# GEN.net
KiCad netlist of a schematic drawn in Altium Designer
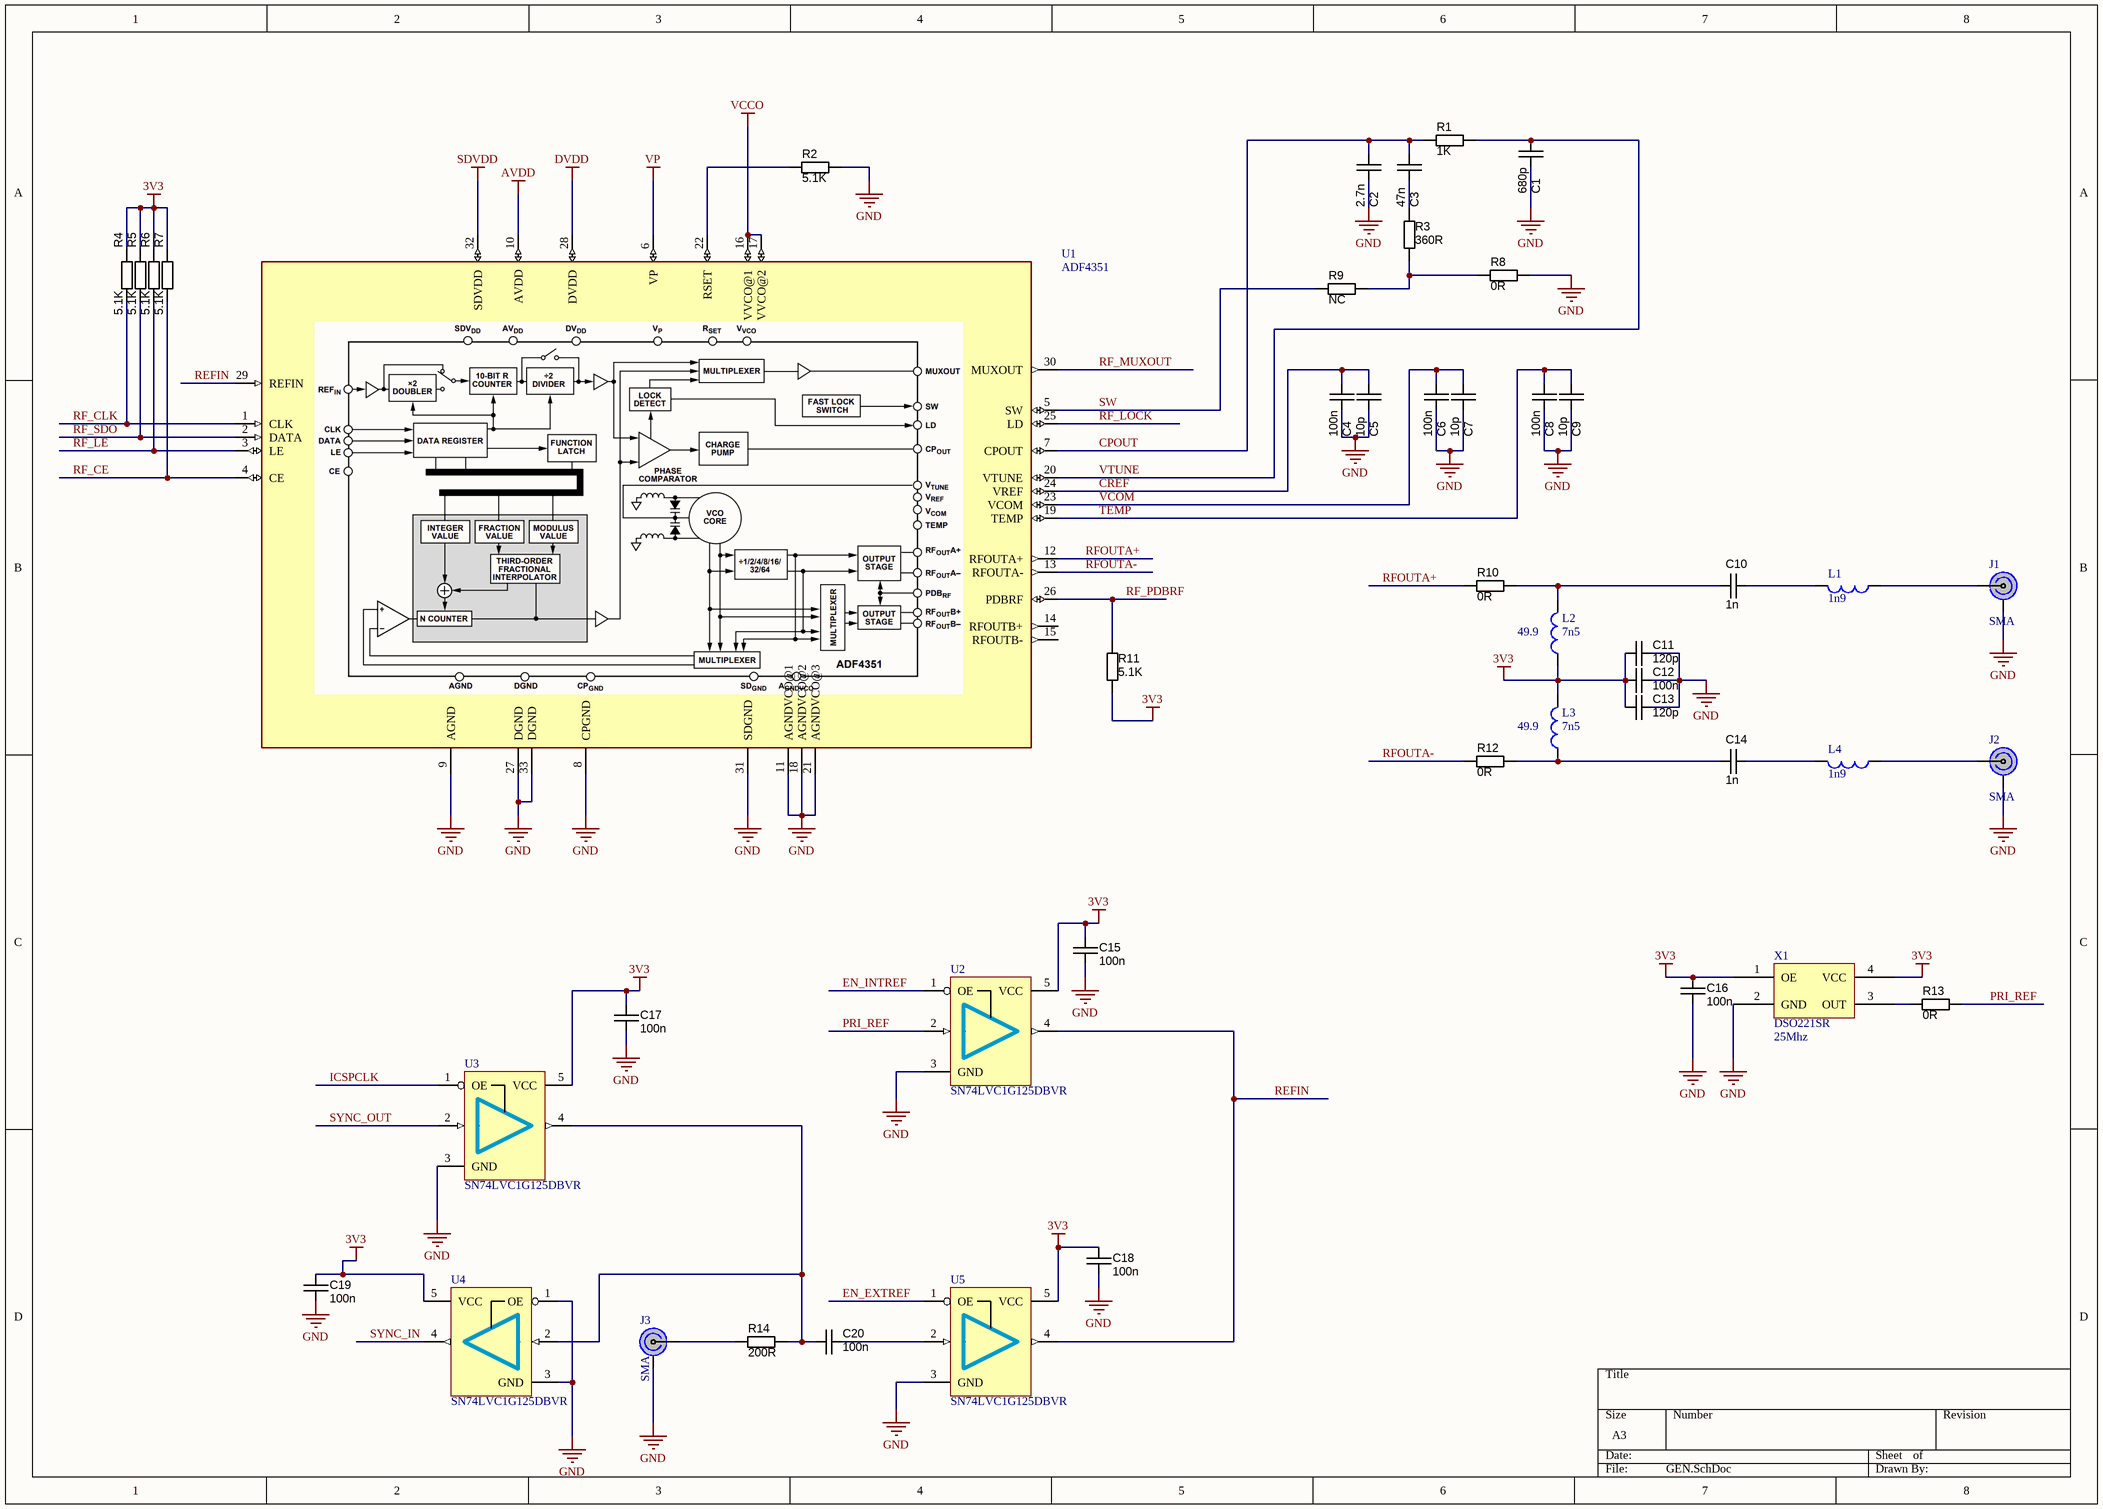
[diagram p0: GEN.SchDoc]

(export (version "E")
  (design (tool "Eeschema 10.0.6"))
  (components
    (comp (ref "C1")
      (value "680p")
      (footprint "CAPC1005N")
      (description "Capacitor SMD Cer 10nF 10% 16V X7R 0402")
      (fields (field (name "TOLERANCE") "±10%"))
      (libsource (lib "PBL - Capacitors") (part "CAPC_10n_0402_16V_10%"))
    )
    (comp (ref "C2")
      (value "2.7n")
      (footprint "CAPC1005N")
      (description "Capacitor SMD Cer 10nF 10% 16V X7R 0402")
      (fields (field (name "TOLERANCE") "±10%"))
      (libsource (lib "PBL - Capacitors") (part "CAPC_10n_0402_16V_10%"))
    )
    (comp (ref "C3")
      (value "47n")
      (footprint "CAPC1005N")
      (description "Capacitor SMD Cer 10nF 10% 16V X7R 0402")
      (fields (field (name "TOLERANCE") "±10%"))
      (libsource (lib "PBL - Capacitors") (part "CAPC_10n_0402_16V_10%"))
    )
    (comp (ref "C4")
      (value "100n")
      (footprint "CAPC1005N")
      (description "Capacitor SMD Cer 10nF 10% 16V X7R 0402")
      (fields (field (name "TOLERANCE") "±10%"))
      (libsource (lib "PBL - Capacitors") (part "CAPC_10n_0402_16V_10%"))
    )
    (comp (ref "C5")
      (value "10p")
      (footprint "CAPC1005N")
      (description "Capacitor SMD Cer 10nF 10% 16V X7R 0402")
      (fields (field (name "TOLERANCE") "±10%"))
      (libsource (lib "PBL - Capacitors") (part "CAPC_10n_0402_16V_10%"))
    )
    (comp (ref "C6")
      (value "100n")
      (footprint "CAPC1005N")
      (description "Capacitor SMD Cer 10nF 10% 16V X7R 0402")
      (fields (field (name "TOLERANCE") "±10%"))
      (libsource (lib "PBL - Capacitors") (part "CAPC_10n_0402_16V_10%"))
    )
    (comp (ref "C7")
      (value "10p")
      (footprint "CAPC1005N")
      (description "Capacitor SMD Cer 10nF 10% 16V X7R 0402")
      (fields (field (name "TOLERANCE") "±10%"))
      (libsource (lib "PBL - Capacitors") (part "CAPC_10n_0402_16V_10%"))
    )
    (comp (ref "C8")
      (value "100n")
      (footprint "CAPC1005N")
      (description "Capacitor SMD Cer 10nF 10% 16V X7R 0402")
      (fields (field (name "TOLERANCE") "±10%"))
      (libsource (lib "PBL - Capacitors") (part "CAPC_10n_0402_16V_10%"))
    )
    (comp (ref "C9")
      (value "10p")
      (footprint "CAPC1005N")
      (description "Capacitor SMD Cer 10nF 10% 16V X7R 0402")
      (fields (field (name "TOLERANCE") "±10%"))
      (libsource (lib "PBL - Capacitors") (part "CAPC_10n_0402_16V_10%"))
    )
    (comp (ref "C10")
      (value "1n")
      (footprint "CAPC1005N")
      (description "Capacitor SMD Cer 10nF 10% 16V X7R 0402")
      (fields (field (name "TOLERANCE") "±10%"))
      (libsource (lib "PBL - Capacitors") (part "CAPC_10n_0402_16V_10%"))
    )
    (comp (ref "C11")
      (value "120p")
      (footprint "CAPC1005N")
      (description "Capacitor SMD Cer 10nF 10% 16V X7R 0402")
      (fields (field (name "TOLERANCE") "±10%"))
      (libsource (lib "PBL - Capacitors") (part "CAPC_10n_0402_16V_10%"))
    )
    (comp (ref "C12")
      (value "100n")
      (footprint "CAPC1005N")
      (description "Capacitor SMD Cer 10nF 10% 16V X7R 0402")
      (fields (field (name "TOLERANCE") "±10%"))
      (libsource (lib "PBL - Capacitors") (part "CAPC_10n_0402_16V_10%"))
    )
    (comp (ref "C13")
      (value "120p")
      (footprint "CAPC1005N")
      (description "Capacitor SMD Cer 10nF 10% 16V X7R 0402")
      (fields (field (name "TOLERANCE") "±10%"))
      (libsource (lib "PBL - Capacitors") (part "CAPC_10n_0402_16V_10%"))
    )
    (comp (ref "C14")
      (value "1n")
      (footprint "CAPC1005N")
      (description "Capacitor SMD Cer 10nF 10% 16V X7R 0402")
      (fields (field (name "TOLERANCE") "±10%"))
      (libsource (lib "PBL - Capacitors") (part "CAPC_10n_0402_16V_10%"))
    )
    (comp (ref "C15")
      (value "100n")
      (footprint "CAPC1005N")
      (description "Capacitor SMD Cer 10nF 10% 16V X7R 0402")
      (fields (field (name "TOLERANCE") "±10%"))
      (libsource (lib "PBL - Capacitors") (part "CAPC_10n_0402_16V_10%"))
    )
    (comp (ref "C16")
      (value "100n")
      (footprint "CAPC1005N")
      (description "Capacitor SMD Cer 10nF 10% 16V X7R 0402")
      (fields (field (name "TOLERANCE") "±10%"))
      (libsource (lib "PBL - Capacitors") (part "CAPC_10n_0402_16V_10%"))
    )
    (comp (ref "C17")
      (value "100n")
      (footprint "CAPC1005N")
      (description "Capacitor SMD Cer 10nF 10% 16V X7R 0402")
      (fields (field (name "TOLERANCE") "±10%"))
      (libsource (lib "PBL - Capacitors") (part "CAPC_10n_0402_16V_10%"))
    )
    (comp (ref "C18")
      (value "100n")
      (footprint "CAPC1005N")
      (description "Capacitor SMD Cer 10nF 10% 16V X7R 0402")
      (fields (field (name "TOLERANCE") "±10%"))
      (libsource (lib "PBL - Capacitors") (part "CAPC_10n_0402_16V_10%"))
    )
    (comp (ref "C19")
      (value "100n")
      (footprint "CAPC1005N")
      (description "Capacitor SMD Cer 10nF 10% 16V X7R 0402")
      (fields (field (name "TOLERANCE") "±10%"))
      (libsource (lib "PBL - Capacitors") (part "CAPC_10n_0402_16V_10%"))
    )
    (comp (ref "C20")
      (value "100n")
      (footprint "CAPC1005N")
      (description "Capacitor SMD Cer 10nF 10% 16V X7R 0402")
      (fields (field (name "TOLERANCE") "±10%"))
      (libsource (lib "PBL - Capacitors") (part "CAPC_10n_0402_16V_10%"))
    )
    (comp (ref "J1") (value "SMA") (footprint "BWSMA-KWE-Z001") (libsource (lib "") (part "SMA Connector_1")))
    (comp (ref "J2") (value "SMA") (footprint "BWSMA-KWE-Z001") (libsource (lib "") (part "SMA Connector_1")))
    (comp (ref "J3")
      (value "SMA")
      (footprint "BWSMA-KWE-Z001")
      (libsource (lib "cvlib") (part "SMA Connector"))
    )
    (comp (ref "L1")
      (value "1n9")
      (footprint "0402_Inductor")
      (libsource (lib "cvlib") (part "inductor_smd"))
    )
    (comp (ref "L2")
      (value "7n5")
      (footprint "0402_Inductor")
      (libsource (lib "cvlib") (part "inductor_smd"))
    )
    (comp (ref "L3")
      (value "7n5")
      (footprint "0402_Inductor")
      (libsource (lib "cvlib") (part "inductor_smd"))
    )
    (comp (ref "L4")
      (value "1n9")
      (footprint "0402_Inductor")
      (libsource (lib "cvlib") (part "inductor_smd"))
    )
    (comp (ref "R1")
      (value "1K")
      (footprint "RESC1005N")
      (description "Resistor SMD chip 3.3k Ohm 0.063W 5% 0402")
      (fields (field (name "TOLERANCE") "±5%") (field (name "Comment") "Thick Film"))
      (libsource (lib "") (part "RES_3K3_0402_5%_1"))
    )
    (comp (ref "R2")
      (value "5.1K")
      (footprint "RESC1005N")
      (description "Resistor SMD chip 3.3k Ohm 0.063W 5% 0402")
      (fields (field (name "TOLERANCE") "±5%") (field (name "Comment") "Thick Film"))
      (libsource (lib "") (part "RES_3K3_0402_5%_1"))
    )
    (comp (ref "R3")
      (value "360R")
      (footprint "RESC1005N")
      (description "Resistor SMD chip 3.3k Ohm 0.063W 5% 0402")
      (fields (field (name "TOLERANCE") "±5%") (field (name "Comment") "Thick Film"))
      (libsource (lib "PBL - Resistors") (part "RES_3K3_0402_5%"))
    )
    (comp (ref "R4")
      (value "5.1K")
      (footprint "RESC1005N")
      (description "Resistor SMD chip 3.3k Ohm 0.063W 5% 0402")
      (fields (field (name "TOLERANCE") "±5%") (field (name "Comment") "Thick Film"))
      (libsource (lib "PBL - Resistors") (part "RES_3K3_0402_5%"))
    )
    (comp (ref "R5")
      (value "5.1K")
      (footprint "RESC1005N")
      (description "Resistor SMD chip 3.3k Ohm 0.063W 5% 0402")
      (fields (field (name "TOLERANCE") "±5%") (field (name "Comment") "Thick Film"))
      (libsource (lib "PBL - Resistors") (part "RES_3K3_0402_5%"))
    )
    (comp (ref "R6")
      (value "5.1K")
      (footprint "RESC1005N")
      (description "Resistor SMD chip 3.3k Ohm 0.063W 5% 0402")
      (fields (field (name "TOLERANCE") "±5%") (field (name "Comment") "Thick Film"))
      (libsource (lib "PBL - Resistors") (part "RES_3K3_0402_5%"))
    )
    (comp (ref "R7")
      (value "5.1K")
      (footprint "RESC1005N")
      (description "Resistor SMD chip 3.3k Ohm 0.063W 5% 0402")
      (fields (field (name "TOLERANCE") "±5%") (field (name "Comment") "Thick Film"))
      (libsource (lib "PBL - Resistors") (part "RES_3K3_0402_5%"))
    )
    (comp (ref "R8")
      (value "0R")
      (footprint "RESC1005N")
      (description "Resistor SMD chip 3.3k Ohm 0.063W 5% 0402")
      (fields (field (name "TOLERANCE") "±5%") (field (name "Comment") "Thick Film"))
      (libsource (lib "") (part "RES_3K3_0402_5%_2"))
    )
    (comp (ref "R9")
      (value "NC")
      (footprint "RESC1005N")
      (description "Resistor SMD chip 3.3k Ohm 0.063W 5% 0402")
      (fields (field (name "TOLERANCE") "±5%") (field (name "Comment") "Thick Film"))
      (libsource (lib "") (part "RES_3K3_0402_5%_2"))
    )
    (comp (ref "R10")
      (value "0R")
      (footprint "RESC1005N")
      (description "Resistor SMD chip 3.3k Ohm 0.063W 5% 0402")
      (fields (field (name "TOLERANCE") "±5%") (field (name "Comment") "Thick Film"))
      (libsource (lib "") (part "RES_3K3_0402_5%_1"))
    )
    (comp (ref "R11")
      (value "5.1K")
      (footprint "RESC1005N")
      (description "Resistor SMD chip 3.3k Ohm 0.063W 5% 0402")
      (fields (field (name "TOLERANCE") "±5%") (field (name "Comment") "Thick Film"))
      (libsource (lib "PBL - Resistors") (part "RES_3K3_0402_5%"))
    )
    (comp (ref "R12")
      (value "0R")
      (footprint "RESC1005N")
      (description "Resistor SMD chip 3.3k Ohm 0.063W 5% 0402")
      (fields (field (name "TOLERANCE") "±5%") (field (name "Comment") "Thick Film"))
      (libsource (lib "") (part "RES_3K3_0402_5%_1"))
    )
    (comp (ref "R13")
      (value "0R")
      (footprint "RESC1005N")
      (description "Resistor SMD chip 3.3k Ohm 0.063W 5% 0402")
      (fields (field (name "TOLERANCE") "±5%") (field (name "Comment") "Thick Film"))
      (libsource (lib "") (part "RES_3K3_0402_5%_1"))
    )
    (comp (ref "R14")
      (value "200R")
      (footprint "RESC1005N")
      (description "Resistor SMD chip 3.3k Ohm 0.063W 5% 0402")
      (fields (field (name "TOLERANCE") "±5%") (field (name "Comment") "Thick Film"))
      (libsource (lib "") (part "RES_3K3_0402_5%_1"))
    )
    (comp (ref "U1")
      (value "ADF4351")
      (footprint "VQFN32")
      (fields (field (name "MF") "Analog Devices, Inc."))
      (libsource (lib "cvlib") (part "ADF4351"))
    )
    (comp (ref "U2")
      (value "SN74LVC1G125DBVR")
      (footprint "SOT23-5")
      (description "LVC Tristate buffer")
      (libsource (lib "cvlib") (part "SN74LVC1G125DBVR"))
    )
    (comp (ref "U3")
      (value "SN74LVC1G125DBVR")
      (footprint "SOT23-5")
      (description "LVC Tristate buffer")
      (libsource (lib "cvlib") (part "SN74LVC1G125DBVR"))
    )
    (comp (ref "U4")
      (value "SN74LVC1G125DBVR")
      (footprint "SOT23-5")
      (description "LVC Tristate buffer")
      (libsource (lib "") (part "SN74LVC1G125DBVR_1"))
    )
    (comp (ref "U5")
      (value "SN74LVC1G125DBVR")
      (footprint "SOT23-5")
      (description "LVC Tristate buffer")
      (libsource (lib "cvlib") (part "SN74LVC1G125DBVR"))
    )
    (comp (ref "X1")
      (value "DSO221SR")
      (footprint "Active Oscillator 2520")
      (description "Active Oscillator_2520")
      (fields (field (name "ALTIUM_VALUE") "25Mhz"))
      (libsource (lib "Crystal_and_oscillator") (part "Oscillator_2520"))
    )
  )
  (nets
    (net (code "1") (name "/CPOUT") (class "Default")
      (node (ref "C2") (pin "1") (pintype "passive"))
      (node (ref "C3") (pin "1") (pintype "passive"))
      (node (ref "R1") (pin "1") (pinfunction "1_1") (pintype "passive"))
      (node (ref "U1") (pin "7") (pinfunction "CPOUT_7") (pintype "bidirectional"))
    )
    (net (code "2") (name "/CREF") (class "Default")
      (node (ref "C4") (pin "1") (pintype "passive"))
      (node (ref "C5") (pin "1") (pintype "passive"))
      (node (ref "U1") (pin "24") (pinfunction "VREF_24") (pintype "bidirectional"))
    )
    (net (code "3") (name "/EN_EXTREF") (class "Default")
      (node (ref "U5") (pin "1") (pinfunction "OE_1") (pintype "power_in"))
    )
    (net (code "4") (name "/EN_INTREF") (class "Default")
      (node (ref "U2") (pin "1") (pinfunction "OE_1") (pintype "power_in"))
    )
    (net (code "5") (name "/ICSPCLK") (class "Default")
      (node (ref "U3") (pin "1") (pinfunction "OE_1") (pintype "power_in"))
    )
    (net (code "6") (name "/PRI_REF") (class "Default")
      (node (ref "R13") (pin "2") (pinfunction "2_2") (pintype "passive"))
      (node (ref "U2") (pin "2") (pinfunction "2_2") (pintype "input"))
    )
    (net (code "7") (name "/REFIN") (class "Default")
      (node (ref "U1") (pin "29") (pinfunction "REFIN_29") (pintype "input"))
      (node (ref "U2") (pin "4") (pinfunction "4_4") (pintype "output"))
      (node (ref "U5") (pin "4") (pinfunction "4_4") (pintype "output"))
    )
    (net (code "8") (name "/RFOUTA+") (class "Default")
      (node (ref "R10") (pin "1") (pinfunction "1_1") (pintype "passive"))
      (node (ref "U1") (pin "12") (pinfunction "RFOUTA+_12") (pintype "output"))
    )
    (net (code "9") (name "/RFOUTA-") (class "Default")
      (node (ref "R12") (pin "1") (pinfunction "1_1") (pintype "passive"))
      (node (ref "U1") (pin "13") (pinfunction "RFOUTA-_13") (pintype "output"))
    )
    (net (code "10") (name "/RF_CE") (class "Default")
      (node (ref "R7") (pin "1") (pinfunction "1_1") (pintype "passive"))
      (node (ref "U1") (pin "4") (pinfunction "CE_4") (pintype "bidirectional"))
    )
    (net (code "11") (name "/RF_CLK") (class "Default")
      (node (ref "R4") (pin "1") (pinfunction "1_1") (pintype "passive"))
      (node (ref "U1") (pin "1") (pinfunction "CLK_1") (pintype "input"))
    )
    (net (code "12") (name "/RF_LE") (class "Default")
      (node (ref "R6") (pin "1") (pinfunction "1_1") (pintype "passive"))
      (node (ref "U1") (pin "3") (pinfunction "LE_3") (pintype "bidirectional"))
    )
    (net (code "13") (name "/RF_LOCK") (class "Default")
      (node (ref "U1") (pin "25") (pinfunction "LD_25") (pintype "bidirectional"))
    )
    (net (code "14") (name "/RF_MUXOUT") (class "Default")
      (node (ref "U1") (pin "30") (pinfunction "MUXOUT_30") (pintype "output"))
    )
    (net (code "15") (name "/RF_PDBRF") (class "Default")
      (node (ref "R11") (pin "2") (pinfunction "2_2") (pintype "passive"))
      (node (ref "U1") (pin "26") (pinfunction "PDBRF_26") (pintype "bidirectional"))
    )
    (net (code "16") (name "/RF_SDO") (class "Default")
      (node (ref "R5") (pin "1") (pinfunction "1_1") (pintype "passive"))
      (node (ref "U1") (pin "2") (pinfunction "DATA_2") (pintype "input"))
    )
    (net (code "17") (name "/SW") (class "Default")
      (node (ref "R9") (pin "2") (pinfunction "2_2") (pintype "passive"))
      (node (ref "U1") (pin "5") (pinfunction "SW_5") (pintype "bidirectional"))
    )
    (net (code "18") (name "/SYNC_IN") (class "Default")
      (node (ref "U4") (pin "4") (pinfunction "4_4") (pintype "output"))
    )
    (net (code "19") (name "/SYNC_OUT") (class "Default")
      (node (ref "U3") (pin "2") (pinfunction "2_2") (pintype "input"))
    )
    (net (code "20") (name "/TEMP") (class "Default")
      (node (ref "C8") (pin "1") (pintype "passive"))
      (node (ref "C9") (pin "1") (pintype "passive"))
      (node (ref "U1") (pin "19") (pinfunction "TEMP_19") (pintype "bidirectional"))
    )
    (net (code "21") (name "/VCOM") (class "Default")
      (node (ref "C6") (pin "1") (pintype "passive"))
      (node (ref "C7") (pin "1") (pintype "passive"))
      (node (ref "U1") (pin "23") (pinfunction "VCOM_23") (pintype "bidirectional"))
    )
    (net (code "22") (name "/VTUNE") (class "Default")
      (node (ref "C1") (pin "1") (pintype "passive"))
      (node (ref "R1") (pin "2") (pinfunction "2_2") (pintype "passive"))
      (node (ref "U1") (pin "20") (pinfunction "VTUNE_20") (pintype "bidirectional"))
    )
    (net (code "23") (name "3V3") (class "Default")
      (node (ref "C11") (pin "2") (pintype "passive"))
      (node (ref "C12") (pin "2") (pintype "passive"))
      (node (ref "C13") (pin "2") (pintype "passive"))
      (node (ref "C15") (pin "2") (pintype "passive"))
      (node (ref "C16") (pin "2") (pintype "passive"))
      (node (ref "C17") (pin "2") (pintype "passive"))
      (node (ref "C18") (pin "2") (pintype "passive"))
      (node (ref "C19") (pin "2") (pintype "passive"))
      (node (ref "L2") (pin "1") (pinfunction "1_1") (pintype "passive"))
      (node (ref "L3") (pin "2") (pinfunction "2_2") (pintype "passive"))
      (node (ref "R11") (pin "1") (pinfunction "1_1") (pintype "passive"))
      (node (ref "R4") (pin "2") (pinfunction "2_2") (pintype "passive"))
      (node (ref "R5") (pin "2") (pinfunction "2_2") (pintype "passive"))
      (node (ref "R6") (pin "2") (pinfunction "2_2") (pintype "passive"))
      (node (ref "R7") (pin "2") (pinfunction "2_2") (pintype "passive"))
      (node (ref "U2") (pin "5") (pinfunction "VCC_5") (pintype "power_in"))
      (node (ref "U3") (pin "5") (pinfunction "VCC_5") (pintype "power_in"))
      (node (ref "U4") (pin "5") (pinfunction "VCC_5") (pintype "power_in"))
      (node (ref "U5") (pin "5") (pinfunction "VCC_5") (pintype "power_in"))
      (node (ref "X1") (pin "1") (pinfunction "OE_1") (pintype "passive"))
      (node (ref "X1") (pin "4") (pinfunction "VCC_4") (pintype "passive"))
    )
    (net (code "24") (name "AVDD") (class "Default")
      (node (ref "U1") (pin "10") (pinfunction "AVDD_10") (pintype "bidirectional"))
    )
    (net (code "25") (name "DVDD") (class "Default")
      (node (ref "U1") (pin "28") (pinfunction "DVDD_28") (pintype "bidirectional"))
    )
    (net (code "26") (name "GND") (class "Default")
      (node (ref "C1") (pin "2") (pintype "passive"))
      (node (ref "C11") (pin "1") (pintype "passive"))
      (node (ref "C12") (pin "1") (pintype "passive"))
      (node (ref "C13") (pin "1") (pintype "passive"))
      (node (ref "C15") (pin "1") (pintype "passive"))
      (node (ref "C16") (pin "1") (pintype "passive"))
      (node (ref "C17") (pin "1") (pintype "passive"))
      (node (ref "C18") (pin "1") (pintype "passive"))
      (node (ref "C19") (pin "1") (pintype "passive"))
      (node (ref "C2") (pin "2") (pintype "passive"))
      (node (ref "C4") (pin "2") (pintype "passive"))
      (node (ref "C5") (pin "2") (pintype "passive"))
      (node (ref "C6") (pin "2") (pintype "passive"))
      (node (ref "C7") (pin "2") (pintype "passive"))
      (node (ref "C8") (pin "2") (pintype "passive"))
      (node (ref "C9") (pin "2") (pintype "passive"))
      (node (ref "J1") (pin "2") (pinfunction "2_2") (pintype "passive"))
      (node (ref "J2") (pin "2") (pinfunction "2_2") (pintype "passive"))
      (node (ref "J3") (pin "2") (pinfunction "2_2") (pintype "passive"))
      (node (ref "R2") (pin "2") (pinfunction "2_2") (pintype "passive"))
      (node (ref "R8") (pin "1") (pinfunction "1_1") (pintype "passive"))
      (node (ref "U1") (pin "11") (pinfunction "AGNDVCO@1_11") (pintype "passive"))
      (node (ref "U1") (pin "18") (pinfunction "AGNDVCO@2_18") (pintype "passive"))
      (node (ref "U1") (pin "21") (pinfunction "AGNDVCO@3_21") (pintype "passive"))
      (node (ref "U1") (pin "27") (pinfunction "DGND_27") (pintype "passive"))
      (node (ref "U1") (pin "31") (pinfunction "SDGND_31") (pintype "passive"))
      (node (ref "U1") (pin "33") (pinfunction "DGND_33") (pintype "passive"))
      (node (ref "U1") (pin "8") (pinfunction "CPGND_8") (pintype "passive"))
      (node (ref "U1") (pin "9") (pinfunction "AGND_9") (pintype "passive"))
      (node (ref "U2") (pin "3") (pinfunction "GND_3") (pintype "power_in"))
      (node (ref "U3") (pin "3") (pinfunction "GND_3") (pintype "power_in"))
      (node (ref "U4") (pin "1") (pinfunction "OE_1") (pintype "power_in"))
      (node (ref "U4") (pin "3") (pinfunction "GND_3") (pintype "power_in"))
      (node (ref "U5") (pin "3") (pinfunction "GND_3") (pintype "power_in"))
      (node (ref "X1") (pin "2") (pinfunction "GND_2") (pintype "passive"))
    )
    (net (code "27") (name "Net-(C3-Pad2)") (class "Default")
      (node (ref "C3") (pin "2") (pintype "passive"))
      (node (ref "R3") (pin "2") (pinfunction "2_2") (pintype "passive"))
    )
    (net (code "28") (name "Net-(C10-Pad1)") (class "Default")
      (node (ref "C10") (pin "1") (pintype "passive"))
      (node (ref "L1") (pin "2") (pinfunction "2_2") (pintype "passive"))
    )
    (net (code "29") (name "Net-(C10-Pad2)") (class "Default")
      (node (ref "C10") (pin "2") (pintype "passive"))
      (node (ref "L2") (pin "2") (pinfunction "2_2") (pintype "passive"))
      (node (ref "R10") (pin "2") (pinfunction "2_2") (pintype "passive"))
    )
    (net (code "30") (name "Net-(C14-Pad1)") (class "Default")
      (node (ref "C14") (pin "1") (pintype "passive"))
      (node (ref "L4") (pin "2") (pinfunction "2_2") (pintype "passive"))
    )
    (net (code "31") (name "Net-(C14-Pad2)") (class "Default")
      (node (ref "C14") (pin "2") (pintype "passive"))
      (node (ref "L3") (pin "1") (pinfunction "1_1") (pintype "passive"))
      (node (ref "R12") (pin "2") (pinfunction "2_2") (pintype "passive"))
    )
    (net (code "32") (name "Net-(C20-Pad1)") (class "Default")
      (node (ref "C20") (pin "1") (pintype "passive"))
      (node (ref "U5") (pin "2") (pinfunction "2_2") (pintype "input"))
    )
    (net (code "33") (name "Net-(C20-Pad2)") (class "Default")
      (node (ref "C20") (pin "2") (pintype "passive"))
      (node (ref "R14") (pin "2") (pinfunction "2_2") (pintype "passive"))
      (node (ref "U3") (pin "4") (pinfunction "4_4") (pintype "output"))
      (node (ref "U4") (pin "2") (pinfunction "2_2") (pintype "input"))
    )
    (net (code "34") (name "Net-(J1-Pad1)") (class "Default")
      (node (ref "J1") (pin "1") (pinfunction "1_1") (pintype "passive"))
      (node (ref "L1") (pin "1") (pinfunction "1_1") (pintype "passive"))
    )
    (net (code "35") (name "Net-(J2-Pad1)") (class "Default")
      (node (ref "J2") (pin "1") (pinfunction "1_1") (pintype "passive"))
      (node (ref "L4") (pin "1") (pinfunction "1_1") (pintype "passive"))
    )
    (net (code "36") (name "Net-(J3-Pad1)") (class "Default")
      (node (ref "J3") (pin "1") (pinfunction "1_1") (pintype "passive"))
      (node (ref "R14") (pin "1") (pinfunction "1_1") (pintype "passive"))
    )
    (net (code "37") (name "Net-(R3-Pad1)") (class "Default")
      (node (ref "R3") (pin "1") (pinfunction "1_1") (pintype "passive"))
      (node (ref "R8") (pin "2") (pinfunction "2_2") (pintype "passive"))
      (node (ref "R9") (pin "1") (pinfunction "1_1") (pintype "passive"))
    )
    (net (code "38") (name "Net-(U1-RSET)") (class "Default")
      (node (ref "R2") (pin "1") (pinfunction "1_1") (pintype "passive"))
      (node (ref "U1") (pin "22") (pinfunction "RSET_22") (pintype "bidirectional"))
    )
    (net (code "39") (name "Net-(X1-OUT)") (class "Default")
      (node (ref "R13") (pin "1") (pinfunction "1_1") (pintype "passive"))
      (node (ref "X1") (pin "3") (pinfunction "OUT_3") (pintype "passive"))
    )
    (net (code "40") (name "SDVDD") (class "Default")
      (node (ref "U1") (pin "32") (pinfunction "SDVDD_32") (pintype "bidirectional"))
    )
    (net (code "41") (name "VCCO") (class "Default")
      (node (ref "U1") (pin "16") (pinfunction "VVCO@1_16") (pintype "bidirectional"))
      (node (ref "U1") (pin "17") (pinfunction "VVCO@2_17") (pintype "bidirectional"))
    )
    (net (code "42") (name "VP") (class "Default")
      (node (ref "U1") (pin "6") (pinfunction "VP_6") (pintype "bidirectional"))
    )
    (net (code "43") (name "unconnected-(U1-RFOUTB+-Pad14)") (class "Default")
      (node (ref "U1") (pin "14") (pinfunction "RFOUTB+_14") (pintype "output"))
    )
    (net (code "44") (name "unconnected-(U1-RFOUTB--Pad15)") (class "Default")
      (node (ref "U1") (pin "15") (pinfunction "RFOUTB-_15") (pintype "output"))
    )
  )
)
